# RH040_2.net
KiCad netlist of a schematic drawn in EAGLE
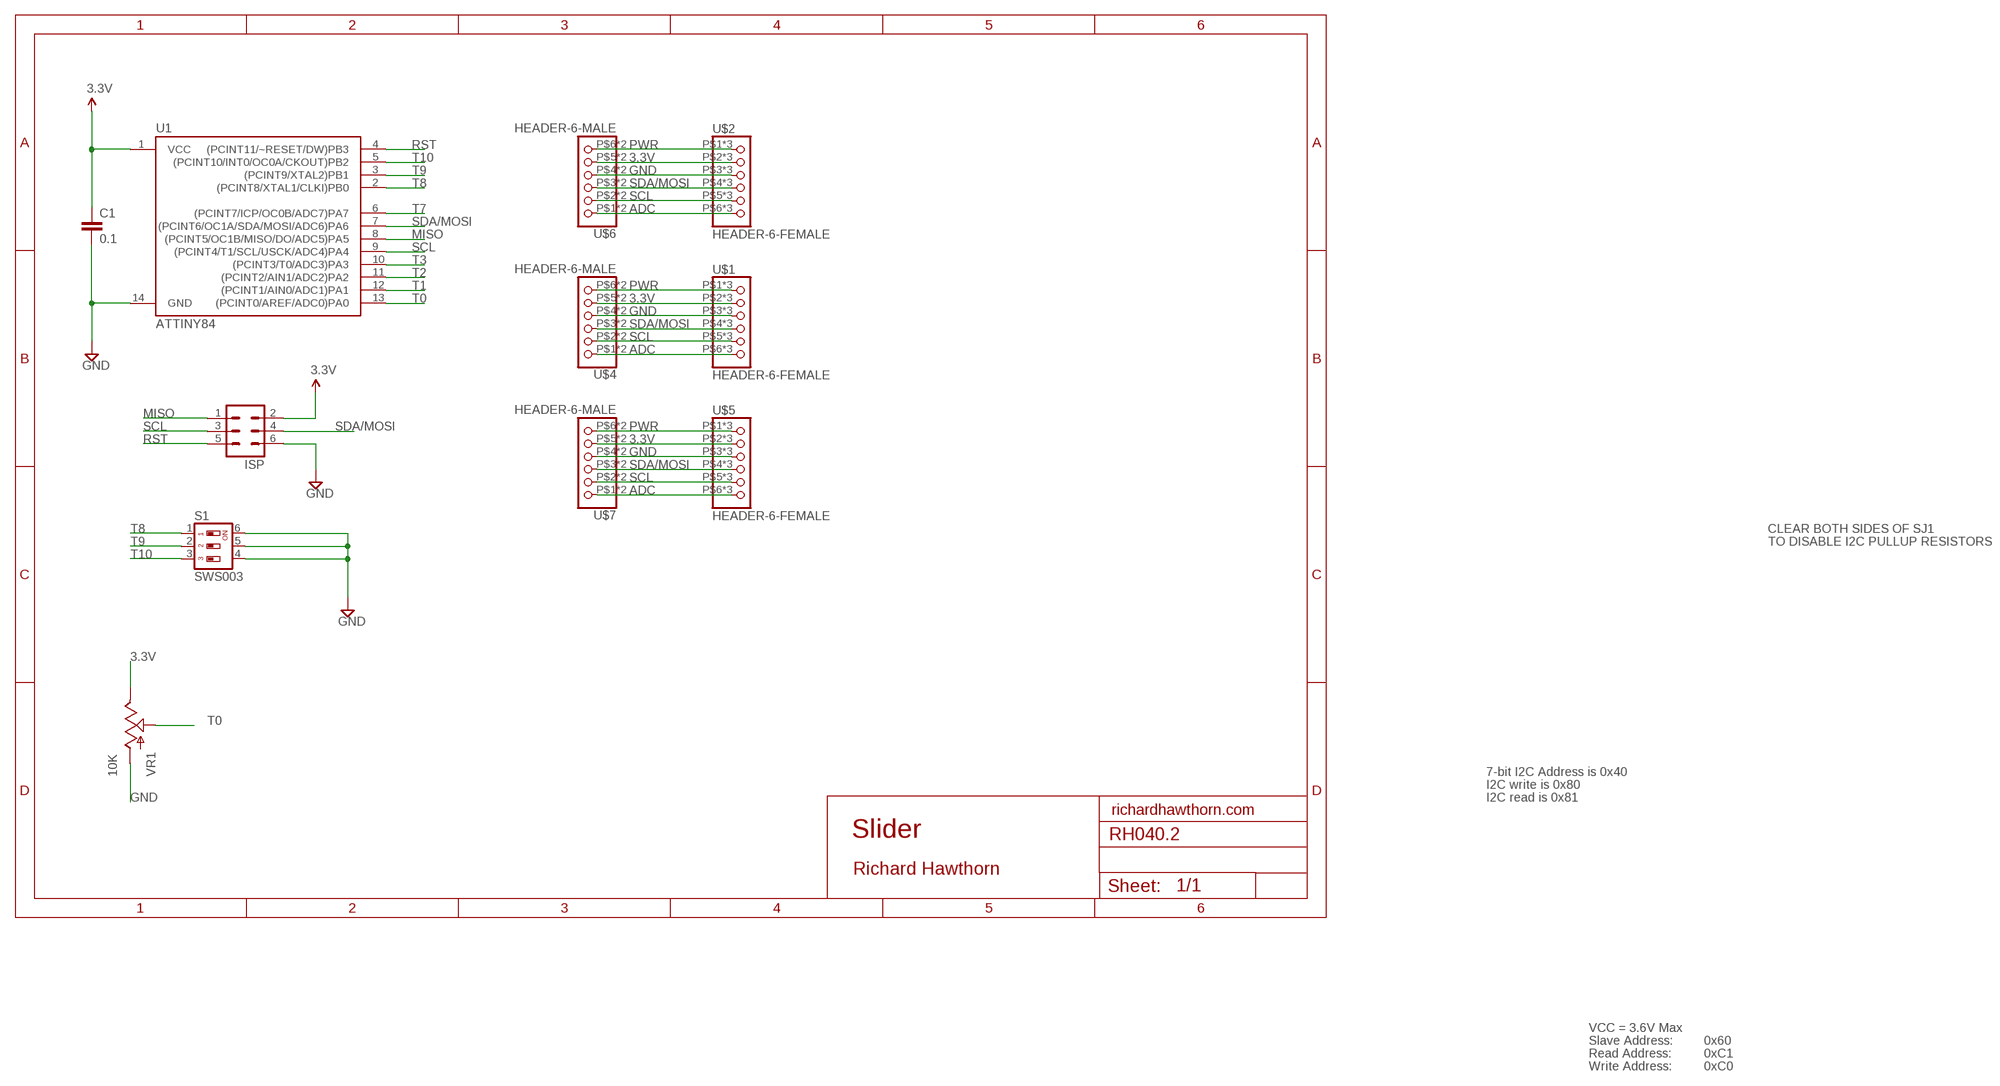
[diagram p0: schematic, sheet 1]

(export (version "E")
  (design (tool "Eeschema 10.0.6"))
  (components
    (comp (ref "C1")
      (value "0.1")
      (footprint "eagle-import:0603-CAP")
      (libsource (lib "eagle-import") (part "CAP0603-CAP"))
    )
    (comp (ref "ISP")
      (value "MA03-2")
      (footprint "eagle-import:MA03-2")
      (libsource (lib "eagle-import") (part "MA03-2"))
    )
    (comp (ref "S1")
      (value "SWS003")
      (footprint "eagle-import:SMS-003")
      (libsource (lib "eagle-import") (part "SWS003"))
    )
    (comp (ref "U$1")
      (value "HEADER-6-FEMALE")
      (footprint "eagle-import:2MMHEADER6")
      (libsource (lib "eagle-import") (part "HEADER-6-FEMALE"))
    )
    (comp (ref "U$2")
      (value "HEADER-6-FEMALE")
      (footprint "eagle-import:2MMHEADER6")
      (libsource (lib "eagle-import") (part "HEADER-6-FEMALE"))
    )
    (comp (ref "U$4")
      (value "HEADER-6-MALE")
      (footprint "eagle-import:2MMHEADERPIN6")
      (libsource (lib "eagle-import") (part "HEADER-6-MALE"))
    )
    (comp (ref "U$5")
      (value "HEADER-6-FEMALE")
      (footprint "eagle-import:2MMHEADER6")
      (libsource (lib "eagle-import") (part "HEADER-6-FEMALE"))
    )
    (comp (ref "U$6")
      (value "HEADER-6-MALE")
      (footprint "eagle-import:2MMHEADERPIN6")
      (libsource (lib "eagle-import") (part "HEADER-6-MALE"))
    )
    (comp (ref "U$7")
      (value "HEADER-6-MALE")
      (footprint "eagle-import:2MMHEADERPIN6")
      (libsource (lib "eagle-import") (part "HEADER-6-MALE"))
    )
    (comp (ref "U1")
      (value "ATTINY84")
      (footprint "eagle-import:SO14")
      (libsource (lib "eagle-import") (part "ATTINY84"))
    )
    (comp (ref "VR1")
      (value "10K")
      (footprint "eagle-import:SLIDER-MEDIUM-KIT")
      (libsource (lib "eagle-import") (part "SLIDER30MM-KIT"))
    )
  )
  (nets
    (net (code "1") (name "/ADC") (class "Default")
      (node (ref "U$1") (pin "P$14") (pinfunction "6_P$14") (pintype "passive"))
      (node (ref "U$1") (pin "P$22") (pinfunction "6_P$22") (pintype "passive"))
      (node (ref "U$1") (pin "P$6") (pinfunction "6_P$6") (pintype "passive"))
      (node (ref "U$2") (pin "P$14") (pinfunction "6_P$14") (pintype "passive"))
      (node (ref "U$2") (pin "P$22") (pinfunction "6_P$22") (pintype "passive"))
      (node (ref "U$2") (pin "P$6") (pinfunction "6_P$6") (pintype "passive"))
      (node (ref "U$4") (pin "P$1") (pinfunction "1_P$1") (pintype "passive"))
      (node (ref "U$4") (pin "P$9") (pinfunction "1_P$9") (pintype "passive"))
      (node (ref "U$5") (pin "P$14") (pinfunction "6_P$14") (pintype "passive"))
      (node (ref "U$5") (pin "P$22") (pinfunction "6_P$22") (pintype "passive"))
      (node (ref "U$5") (pin "P$6") (pinfunction "6_P$6") (pintype "passive"))
      (node (ref "U$6") (pin "P$1") (pinfunction "1_P$1") (pintype "passive"))
      (node (ref "U$6") (pin "P$9") (pinfunction "1_P$9") (pintype "passive"))
      (node (ref "U$7") (pin "P$1") (pinfunction "1_P$1") (pintype "passive"))
      (node (ref "U$7") (pin "P$9") (pinfunction "1_P$9") (pintype "passive"))
    )
    (net (code "2") (name "/MISO") (class "Default")
      (node (ref "ISP") (pin "1") (pinfunction "1_1") (pintype "passive"))
      (node (ref "U1") (pin "8") (pinfunction "(PCINT5/OC1B/MISO/DO/ADC5)PA5_8") (pintype "bidirectional"))
    )
    (net (code "3") (name "/PWR") (class "Default")
      (node (ref "U$1") (pin "P$1") (pinfunction "1_P$1") (pintype "passive"))
      (node (ref "U$1") (pin "P$17") (pinfunction "1_P$17") (pintype "passive"))
      (node (ref "U$1") (pin "P$9") (pinfunction "1_P$9") (pintype "passive"))
      (node (ref "U$2") (pin "P$1") (pinfunction "1_P$1") (pintype "passive"))
      (node (ref "U$2") (pin "P$17") (pinfunction "1_P$17") (pintype "passive"))
      (node (ref "U$2") (pin "P$9") (pinfunction "1_P$9") (pintype "passive"))
      (node (ref "U$4") (pin "P$14") (pinfunction "6_P$14") (pintype "passive"))
      (node (ref "U$4") (pin "P$6") (pinfunction "6_P$6") (pintype "passive"))
      (node (ref "U$5") (pin "P$1") (pinfunction "1_P$1") (pintype "passive"))
      (node (ref "U$5") (pin "P$17") (pinfunction "1_P$17") (pintype "passive"))
      (node (ref "U$5") (pin "P$9") (pinfunction "1_P$9") (pintype "passive"))
      (node (ref "U$6") (pin "P$14") (pinfunction "6_P$14") (pintype "passive"))
      (node (ref "U$6") (pin "P$6") (pinfunction "6_P$6") (pintype "passive"))
      (node (ref "U$7") (pin "P$14") (pinfunction "6_P$14") (pintype "passive"))
      (node (ref "U$7") (pin "P$6") (pinfunction "6_P$6") (pintype "passive"))
    )
    (net (code "4") (name "/RST") (class "Default")
      (node (ref "ISP") (pin "5") (pinfunction "5_5") (pintype "passive"))
      (node (ref "U1") (pin "4") (pinfunction "(PCINT11/~{RESET/DW})PB3_4") (pintype "bidirectional"))
    )
    (net (code "5") (name "/SCL") (class "Default")
      (node (ref "ISP") (pin "3") (pinfunction "3_3") (pintype "passive"))
      (node (ref "U$1") (pin "P$13") (pinfunction "5_P$13") (pintype "passive"))
      (node (ref "U$1") (pin "P$21") (pinfunction "5_P$21") (pintype "passive"))
      (node (ref "U$1") (pin "P$5") (pinfunction "5_P$5") (pintype "passive"))
      (node (ref "U$2") (pin "P$13") (pinfunction "5_P$13") (pintype "passive"))
      (node (ref "U$2") (pin "P$21") (pinfunction "5_P$21") (pintype "passive"))
      (node (ref "U$2") (pin "P$5") (pinfunction "5_P$5") (pintype "passive"))
      (node (ref "U$4") (pin "P$10") (pinfunction "2_P$10") (pintype "passive"))
      (node (ref "U$4") (pin "P$2") (pinfunction "2_P$2") (pintype "passive"))
      (node (ref "U$5") (pin "P$13") (pinfunction "5_P$13") (pintype "passive"))
      (node (ref "U$5") (pin "P$21") (pinfunction "5_P$21") (pintype "passive"))
      (node (ref "U$5") (pin "P$5") (pinfunction "5_P$5") (pintype "passive"))
      (node (ref "U$6") (pin "P$10") (pinfunction "2_P$10") (pintype "passive"))
      (node (ref "U$6") (pin "P$2") (pinfunction "2_P$2") (pintype "passive"))
      (node (ref "U$7") (pin "P$10") (pinfunction "2_P$10") (pintype "passive"))
      (node (ref "U$7") (pin "P$2") (pinfunction "2_P$2") (pintype "passive"))
      (node (ref "U1") (pin "9") (pinfunction "(PCINT4/T1/SCL/USCK/ADC4)PA4_9") (pintype "bidirectional"))
    )
    (net (code "6") (name "/SDA{slash}MOSI") (class "Default")
      (node (ref "ISP") (pin "4") (pinfunction "4_4") (pintype "passive"))
      (node (ref "U$1") (pin "P$12") (pinfunction "4_P$12") (pintype "passive"))
      (node (ref "U$1") (pin "P$20") (pinfunction "4_P$20") (pintype "passive"))
      (node (ref "U$1") (pin "P$4") (pinfunction "4_P$4") (pintype "passive"))
      (node (ref "U$2") (pin "P$12") (pinfunction "4_P$12") (pintype "passive"))
      (node (ref "U$2") (pin "P$20") (pinfunction "4_P$20") (pintype "passive"))
      (node (ref "U$2") (pin "P$4") (pinfunction "4_P$4") (pintype "passive"))
      (node (ref "U$4") (pin "P$11") (pinfunction "3_P$11") (pintype "passive"))
      (node (ref "U$4") (pin "P$3") (pinfunction "3_P$3") (pintype "passive"))
      (node (ref "U$5") (pin "P$12") (pinfunction "4_P$12") (pintype "passive"))
      (node (ref "U$5") (pin "P$20") (pinfunction "4_P$20") (pintype "passive"))
      (node (ref "U$5") (pin "P$4") (pinfunction "4_P$4") (pintype "passive"))
      (node (ref "U$6") (pin "P$11") (pinfunction "3_P$11") (pintype "passive"))
      (node (ref "U$6") (pin "P$3") (pinfunction "3_P$3") (pintype "passive"))
      (node (ref "U$7") (pin "P$11") (pinfunction "3_P$11") (pintype "passive"))
      (node (ref "U$7") (pin "P$3") (pinfunction "3_P$3") (pintype "passive"))
      (node (ref "U1") (pin "7") (pinfunction "(PCINT6/OC1A/SDA/MOSI/ADC6)PA6_7") (pintype "bidirectional"))
    )
    (net (code "7") (name "/T0") (class "Default")
      (node (ref "U1") (pin "13") (pinfunction "(PCINT0/AREF/ADC0)PA0_13") (pintype "bidirectional"))
      (node (ref "VR1") (pin "WIPER") (pinfunction "S_WIPER") (pintype "passive"))
    )
    (net (code "8") (name "/T1") (class "Default")
      (node (ref "U1") (pin "12") (pinfunction "(PCINT1/AIN0/ADC1)PA1_12") (pintype "bidirectional"))
    )
    (net (code "9") (name "/T2") (class "Default")
      (node (ref "U1") (pin "11") (pinfunction "(PCINT2/AIN1/ADC2)PA2_11") (pintype "bidirectional"))
    )
    (net (code "10") (name "/T3") (class "Default")
      (node (ref "U1") (pin "10") (pinfunction "(PCINT3/T0/ADC3)PA3_10") (pintype "bidirectional"))
    )
    (net (code "11") (name "/T7") (class "Default")
      (node (ref "U1") (pin "6") (pinfunction "(PCINT7/ICP/OC0B/ADC7)PA7_6") (pintype "bidirectional"))
    )
    (net (code "12") (name "/T8") (class "Default")
      (node (ref "S1") (pin "1") (pinfunction "1_1") (pintype "passive"))
      (node (ref "U1") (pin "2") (pinfunction "(PCINT8/XTAL1/CLKI)PB0_2") (pintype "bidirectional"))
    )
    (net (code "13") (name "/T9") (class "Default")
      (node (ref "S1") (pin "2") (pinfunction "2_2") (pintype "passive"))
      (node (ref "U1") (pin "3") (pinfunction "(PCINT9/XTAL2)PB1_3") (pintype "bidirectional"))
    )
    (net (code "14") (name "/T10") (class "Default")
      (node (ref "S1") (pin "3") (pinfunction "3_3") (pintype "passive"))
      (node (ref "U1") (pin "5") (pinfunction "(PCINT10/INT0/OC0A/CKOUT)PB2_5") (pintype "bidirectional"))
    )
    (net (code "15") (name "3.3V") (class "Default")
      (node (ref "C1") (pin "1") (pinfunction "1_1") (pintype "passive"))
      (node (ref "ISP") (pin "2") (pinfunction "2_2") (pintype "passive"))
      (node (ref "U$1") (pin "P$10") (pinfunction "2_P$10") (pintype "passive"))
      (node (ref "U$1") (pin "P$18") (pinfunction "2_P$18") (pintype "passive"))
      (node (ref "U$1") (pin "P$2") (pinfunction "2_P$2") (pintype "passive"))
      (node (ref "U$2") (pin "P$10") (pinfunction "2_P$10") (pintype "passive"))
      (node (ref "U$2") (pin "P$18") (pinfunction "2_P$18") (pintype "passive"))
      (node (ref "U$2") (pin "P$2") (pinfunction "2_P$2") (pintype "passive"))
      (node (ref "U$4") (pin "P$13") (pinfunction "5_P$13") (pintype "passive"))
      (node (ref "U$4") (pin "P$5") (pinfunction "5_P$5") (pintype "passive"))
      (node (ref "U$5") (pin "P$10") (pinfunction "2_P$10") (pintype "passive"))
      (node (ref "U$5") (pin "P$18") (pinfunction "2_P$18") (pintype "passive"))
      (node (ref "U$5") (pin "P$2") (pinfunction "2_P$2") (pintype "passive"))
      (node (ref "U$6") (pin "P$13") (pinfunction "5_P$13") (pintype "passive"))
      (node (ref "U$6") (pin "P$5") (pinfunction "5_P$5") (pintype "passive"))
      (node (ref "U$7") (pin "P$13") (pinfunction "5_P$13") (pintype "passive"))
      (node (ref "U$7") (pin "P$5") (pinfunction "5_P$5") (pintype "passive"))
      (node (ref "U1") (pin "1") (pinfunction "VCC_1") (pintype "bidirectional"))
      (node (ref "VR1") (pin "TOP") (pinfunction "E_TOP") (pintype "passive"))
    )
    (net (code "16") (name "GND") (class "Default")
      (node (ref "C1") (pin "2") (pinfunction "2_2") (pintype "passive"))
      (node (ref "ISP") (pin "6") (pinfunction "6_6") (pintype "passive"))
      (node (ref "S1") (pin "4") (pinfunction "4_4") (pintype "passive"))
      (node (ref "S1") (pin "5") (pinfunction "5_5") (pintype "passive"))
      (node (ref "S1") (pin "6") (pinfunction "6_6") (pintype "passive"))
      (node (ref "U$1") (pin "P$11") (pinfunction "3_P$11") (pintype "passive"))
      (node (ref "U$1") (pin "P$19") (pinfunction "3_P$19") (pintype "passive"))
      (node (ref "U$1") (pin "P$3") (pinfunction "3_P$3") (pintype "passive"))
      (node (ref "U$2") (pin "P$11") (pinfunction "3_P$11") (pintype "passive"))
      (node (ref "U$2") (pin "P$19") (pinfunction "3_P$19") (pintype "passive"))
      (node (ref "U$2") (pin "P$3") (pinfunction "3_P$3") (pintype "passive"))
      (node (ref "U$4") (pin "P$12") (pinfunction "4_P$12") (pintype "passive"))
      (node (ref "U$4") (pin "P$4") (pinfunction "4_P$4") (pintype "passive"))
      (node (ref "U$5") (pin "P$11") (pinfunction "3_P$11") (pintype "passive"))
      (node (ref "U$5") (pin "P$19") (pinfunction "3_P$19") (pintype "passive"))
      (node (ref "U$5") (pin "P$3") (pinfunction "3_P$3") (pintype "passive"))
      (node (ref "U$6") (pin "P$12") (pinfunction "4_P$12") (pintype "passive"))
      (node (ref "U$6") (pin "P$4") (pinfunction "4_P$4") (pintype "passive"))
      (node (ref "U$7") (pin "P$12") (pinfunction "4_P$12") (pintype "passive"))
      (node (ref "U$7") (pin "P$4") (pinfunction "4_P$4") (pintype "passive"))
      (node (ref "U1") (pin "14") (pinfunction "GND_14") (pintype "bidirectional"))
      (node (ref "VR1") (pin "BOTTOM") (pinfunction "A_BOTTOM") (pintype "passive"))
    )
  )
)
